# bank_34.net
KiCad netlist of a schematic drawn in Altium Designer
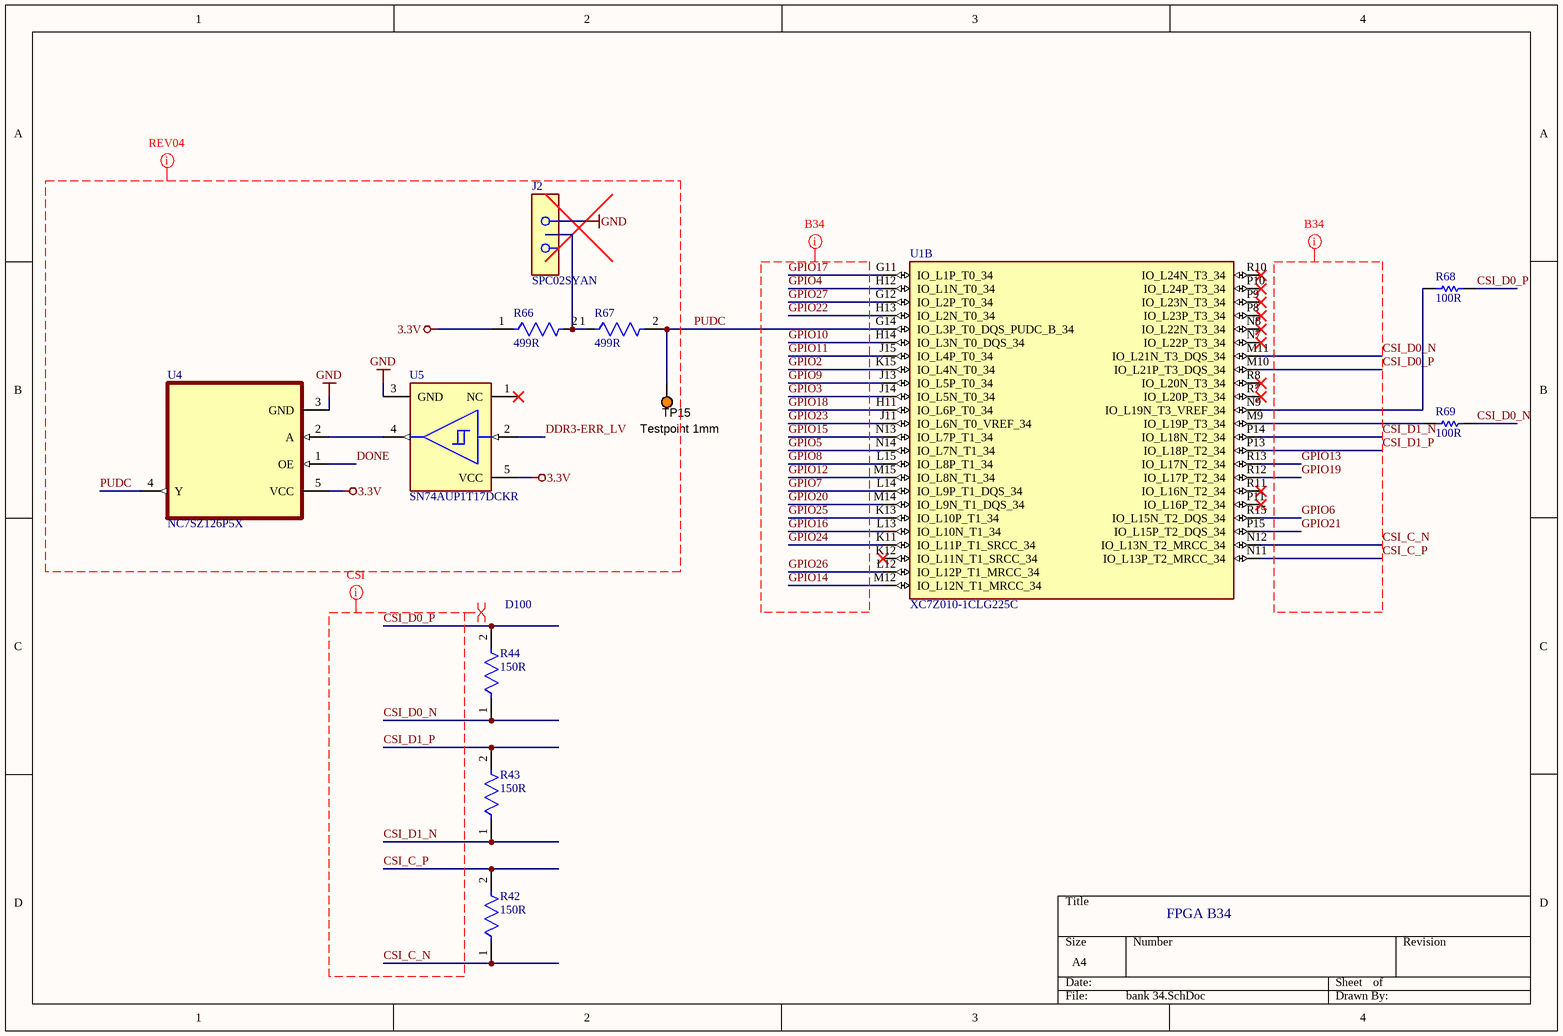
[diagram p0: bank 34.SchDoc]

(export (version "E")
  (design (tool "Eeschema 10.0.6"))
  (components
    (comp (ref "J2")
      (value "SPC02SYAN")
      (footprint "FP-SPC02SYAN-MFG")
      (description "CONN JUMPER SHORTING GOLD FLASH")
      (libsource (lib "Altium Content Vault") (part "728c6cbc3517dff9de184b23a534e16"))
    )
    (comp (ref "R42")
      (value "150R")
      (footprint "FP-RT0402-MFG")
      (description "RES SMD 150 OHM 0.1% 1/16W 0402")
      (fields
        (field (name "MANUFACTURER") "Yageo")
        (field (name "MANUFACTURER PART NUMBER") "RT0402BRD07150RL")
      )
      (libsource (lib "Altium Content Vault") (part "1029c3af85768c4190bb7ad29bc67b5"))
    )
    (comp (ref "R43")
      (value "150R")
      (footprint "FP-RT0402-MFG")
      (description "RES SMD 150 OHM 0.1% 1/16W 0402")
      (fields
        (field (name "MANUFACTURER") "Yageo")
        (field (name "MANUFACTURER PART NUMBER") "RT0402BRD07150RL")
      )
      (libsource (lib "Altium Content Vault") (part "1029c3af85768c4190bb7ad29bc67b5"))
    )
    (comp (ref "R44")
      (value "150R")
      (footprint "FP-RT0402-MFG")
      (description "RES SMD 150 OHM 0.1% 1/16W 0402")
      (fields
        (field (name "MANUFACTURER") "Yageo")
        (field (name "MANUFACTURER PART NUMBER") "RT0402BRD07150RL")
      )
      (libsource (lib "Altium Content Vault") (part "1029c3af85768c4190bb7ad29bc67b5"))
    )
    (comp (ref "R66")
      (value "499R")
      (footprint "FP-RQ731J-IPC_C")
      (description "RQ73 0603 499Ω  0.15W 10ppm/°C 0.1% 75V")
      (fields (field (name "MANUFACTURER") "TE") (field (name "TOLERANCE") "0.1%"))
      (libsource (lib "Altium Content Vault") (part "1029c3af85768c4190bb7ad29bc67b5"))
    )
    (comp (ref "R67")
      (value "499R")
      (footprint "FP-RQ731J-IPC_C")
      (description "RQ73 0603 499Ω  0.15W 10ppm/°C 0.1% 75V")
      (fields (field (name "MANUFACTURER") "TE") (field (name "TOLERANCE") "0.1%"))
      (libsource (lib "Altium Content Vault") (part "1029c3af85768c4190bb7ad29bc67b5"))
    )
    (comp (ref "R68")
      (value "100R")
      (footprint "RESC0603X28X15LL05T05")
      (fields (field (name "PART NUMBER") "CRCW0201100RJNED") (field (name "MANUFACTURER") "Vishay"))
      (libsource (lib "Altium Content Vault") (part "RES"))
    )
    (comp (ref "R69")
      (value "100R")
      (footprint "RESC0603X28X15LL05T05")
      (fields (field (name "PART NUMBER") "CRCW0201100RJNED") (field (name "MANUFACTURER") "Vishay"))
      (libsource (lib "Altium Content Vault") (part "RES"))
    )
    (comp (ref "TP15")
      (value "Testpoint 1mm")
      (footprint "KSTN-5003")
      (description "Test Point, Orange, 1-Pin THD, RoHS")
      (libsource (lib "Altium Content Vault") (part "TESTPOINT_ORANGE"))
    )
    (comp (ref "U1")
      (value "XC7Z010-1CLG225C")
      (footprint "BGA225C80P15X15_1300X1300X150")
      (fields (field (name "MF") "Xilinx Inc.") (field (name "DIGI-KEY_PART_NUMBER") "122-1855-ND"))
      (libsource (lib "XC7Z010-1CLG225C (2)") (part "XC7Z010-1CLG225C"))
    )
    (comp (ref "U4")
      (value "NC7SZ126P5X")
      (footprint "SOT65P210X110-5N")
      (description "Buffer, Non-Inverting 1 Element 1 Bit per Element 3-State Output SC-70-5")
      (fields (field (name "MF") "ON Semiconductor"))
      (libsource (lib "NC7SZ126P5X") (part "NC7SZ126P5X"))
    )
    (comp (ref "U5")
      (value "SN74AUP1T17DCKR")
      (footprint "FP-DCK0005A-IPC_B")
      (description "IC BUF NON-INVERT 3.6V SC70-5")
      (libsource (lib "Altium Content Vault") (part "13663c114c60c392ae5ab8dc83cb180"))
    )
  )
  (nets
    (net (code "1") (name "/CSI_C_N") (class "Default")
      (node (ref "R42") (pin "1") (pinfunction "1_1") (pintype "passive"))
      (node (ref "U1") (pin "N12") (pinfunction "IO_L13N_T2_MRCC_34_N12") (pintype "bidirectional"))
    )
    (net (code "2") (name "/CSI_C_P") (class "Default")
      (node (ref "R42") (pin "2") (pinfunction "2_2") (pintype "passive"))
      (node (ref "U1") (pin "N11") (pinfunction "IO_L13P_T2_MRCC_34_N11") (pintype "bidirectional"))
    )
    (net (code "3") (name "/CSI_D0_N") (class "Default")
      (node (ref "R44") (pin "1") (pinfunction "1_1") (pintype "passive"))
      (node (ref "R69") (pin "2") (pinfunction "2_2") (pintype "passive"))
      (node (ref "U1") (pin "M11") (pinfunction "IO_L21N_T3_DQS_34_M11") (pintype "bidirectional"))
    )
    (net (code "4") (name "/CSI_D0_P") (class "Default")
      (node (ref "R44") (pin "2") (pinfunction "2_2") (pintype "passive"))
      (node (ref "R68") (pin "2") (pinfunction "2_2") (pintype "passive"))
      (node (ref "U1") (pin "M10") (pinfunction "IO_L21P_T3_DQS_34_M10") (pintype "bidirectional"))
    )
    (net (code "5") (name "/CSI_D1_N") (class "Default")
      (node (ref "R43") (pin "1") (pinfunction "1_1") (pintype "passive"))
      (node (ref "U1") (pin "P14") (pinfunction "IO_L18N_T2_34_P14") (pintype "bidirectional"))
    )
    (net (code "6") (name "/CSI_D1_P") (class "Default")
      (node (ref "R43") (pin "2") (pinfunction "2_2") (pintype "passive"))
      (node (ref "U1") (pin "P13") (pinfunction "IO_L18P_T2_34_P13") (pintype "bidirectional"))
    )
    (net (code "7") (name "/DDR3-ERR_LV") (class "Default")
      (node (ref "U5") (pin "2") (pinfunction "A_2") (pintype "input"))
    )
    (net (code "8") (name "/DONE") (class "Default")
      (node (ref "U4") (pin "1") (pinfunction "OE_1") (pintype "input"))
    )
    (net (code "9") (name "/GPIO2") (class "Default")
      (node (ref "U1") (pin "K15") (pinfunction "IO_L4N_T0_34_K15") (pintype "bidirectional"))
    )
    (net (code "10") (name "/GPIO3") (class "Default")
      (node (ref "U1") (pin "J14") (pinfunction "IO_L5N_T0_34_J14") (pintype "bidirectional"))
    )
    (net (code "11") (name "/GPIO4") (class "Default")
      (node (ref "U1") (pin "H12") (pinfunction "IO_L1N_T0_34_H12") (pintype "bidirectional"))
    )
    (net (code "12") (name "/GPIO5") (class "Default")
      (node (ref "U1") (pin "N14") (pinfunction "IO_L7N_T1_34_N14") (pintype "bidirectional"))
    )
    (net (code "13") (name "/GPIO6") (class "Default")
      (node (ref "U1") (pin "R15") (pinfunction "IO_L15N_T2_DQS_34_R15") (pintype "bidirectional"))
    )
    (net (code "14") (name "/GPIO7") (class "Default")
      (node (ref "U1") (pin "L14") (pinfunction "IO_L9P_T1_DQS_34_L14") (pintype "bidirectional"))
    )
    (net (code "15") (name "/GPIO8") (class "Default")
      (node (ref "U1") (pin "L15") (pinfunction "IO_L8P_T1_34_L15") (pintype "bidirectional"))
    )
    (net (code "16") (name "/GPIO9") (class "Default")
      (node (ref "U1") (pin "J13") (pinfunction "IO_L5P_T0_34_J13") (pintype "bidirectional"))
    )
    (net (code "17") (name "/GPIO10") (class "Default")
      (node (ref "U1") (pin "H14") (pinfunction "IO_L3N_T0_DQS_34_H14") (pintype "bidirectional"))
    )
    (net (code "18") (name "/GPIO11") (class "Default")
      (node (ref "U1") (pin "J15") (pinfunction "IO_L4P_T0_34_J15") (pintype "bidirectional"))
    )
    (net (code "19") (name "/GPIO12") (class "Default")
      (node (ref "U1") (pin "M15") (pinfunction "IO_L8N_T1_34_M15") (pintype "bidirectional"))
    )
    (net (code "20") (name "/GPIO13") (class "Default")
      (node (ref "U1") (pin "R13") (pinfunction "IO_L17N_T2_34_R13") (pintype "bidirectional"))
    )
    (net (code "21") (name "/GPIO14") (class "Default")
      (node (ref "U1") (pin "M12") (pinfunction "IO_L12N_T1_MRCC_34_M12") (pintype "bidirectional"))
    )
    (net (code "22") (name "/GPIO15") (class "Default")
      (node (ref "U1") (pin "N13") (pinfunction "IO_L7P_T1_34_N13") (pintype "bidirectional"))
    )
    (net (code "23") (name "/GPIO16") (class "Default")
      (node (ref "U1") (pin "L13") (pinfunction "IO_L10N_T1_34_L13") (pintype "bidirectional"))
    )
    (net (code "24") (name "/GPIO17") (class "Default")
      (node (ref "U1") (pin "G11") (pinfunction "IO_L1P_T0_34_G11") (pintype "bidirectional"))
    )
    (net (code "25") (name "/GPIO18") (class "Default")
      (node (ref "U1") (pin "H11") (pinfunction "IO_L6P_T0_34_H11") (pintype "bidirectional"))
    )
    (net (code "26") (name "/GPIO19") (class "Default")
      (node (ref "U1") (pin "R12") (pinfunction "IO_L17P_T2_34_R12") (pintype "bidirectional"))
    )
    (net (code "27") (name "/GPIO20") (class "Default")
      (node (ref "U1") (pin "M14") (pinfunction "IO_L9N_T1_DQS_34_M14") (pintype "bidirectional"))
    )
    (net (code "28") (name "/GPIO21") (class "Default")
      (node (ref "U1") (pin "P15") (pinfunction "IO_L15P_T2_DQS_34_P15") (pintype "bidirectional"))
    )
    (net (code "29") (name "/GPIO22") (class "Default")
      (node (ref "U1") (pin "H13") (pinfunction "IO_L2N_T0_34_H13") (pintype "bidirectional"))
    )
    (net (code "30") (name "/GPIO23") (class "Default")
      (node (ref "U1") (pin "J11") (pinfunction "IO_L6N_T0_VREF_34_J11") (pintype "bidirectional"))
    )
    (net (code "31") (name "/GPIO24") (class "Default")
      (node (ref "U1") (pin "K11") (pinfunction "IO_L11P_T1_SRCC_34_K11") (pintype "bidirectional"))
    )
    (net (code "32") (name "/GPIO25") (class "Default")
      (node (ref "U1") (pin "K13") (pinfunction "IO_L10P_T1_34_K13") (pintype "bidirectional"))
    )
    (net (code "33") (name "/GPIO26") (class "Default")
      (node (ref "U1") (pin "L12") (pinfunction "IO_L12P_T1_MRCC_34_L12") (pintype "bidirectional"))
    )
    (net (code "34") (name "/GPIO27") (class "Default")
      (node (ref "U1") (pin "G12") (pinfunction "IO_L2P_T0_34_G12") (pintype "bidirectional"))
    )
    (net (code "35") (name "/PUDC") (class "Default")
      (node (ref "R67") (pin "2") (pinfunction "2_2") (pintype "passive"))
      (node (ref "TP15") (pin "1") (pinfunction "1_1") (pintype "passive"))
      (node (ref "U1") (pin "G14") (pinfunction "IO_L3P_T0_DQS_PUDC_B_34_G14") (pintype "bidirectional"))
      (node (ref "U4") (pin "4") (pinfunction "Y_4") (pintype "output"))
    )
    (net (code "36") (name "3.3V") (class "Default")
      (node (ref "R66") (pin "1") (pinfunction "1_1") (pintype "passive"))
      (node (ref "U4") (pin "5") (pinfunction "VCC_5") (pintype "power_in"))
      (node (ref "U5") (pin "5") (pinfunction "VCC_5") (pintype "power_in"))
    )
    (net (code "37") (name "GND") (class "Default")
      (node (ref "U4") (pin "3") (pinfunction "GND_3") (pintype "passive"))
      (node (ref "U5") (pin "3") (pinfunction "GND_3") (pintype "power_in"))
    )
    (net (code "38") (name "Net-(R66-Pad2)") (class "Default")
      (node (ref "R66") (pin "2") (pinfunction "2_2") (pintype "passive"))
      (node (ref "R67") (pin "1") (pinfunction "1_1") (pintype "passive"))
    )
    (net (code "39") (name "Net-(U1B-IO_L19N_T3_VREF_34)") (class "Default")
      (node (ref "R68") (pin "1") (pinfunction "1_1") (pintype "passive"))
      (node (ref "U1") (pin "N9") (pinfunction "IO_L19N_T3_VREF_34_N9") (pintype "bidirectional"))
    )
    (net (code "40") (name "Net-(U1B-IO_L19P_T3_34)") (class "Default")
      (node (ref "R69") (pin "1") (pinfunction "1_1") (pintype "passive"))
      (node (ref "U1") (pin "M9") (pinfunction "IO_L19P_T3_34_M9") (pintype "bidirectional"))
    )
    (net (code "41") (name "Net-(U4-A)") (class "Default")
      (node (ref "U4") (pin "2") (pinfunction "A_2") (pintype "input"))
      (node (ref "U5") (pin "4") (pinfunction "Y_4") (pintype "output"))
    )
    (net (code "42") (name "unconnected-(U1B-IO_L11N_T1_SRCC_34-PadK12)") (class "Default")
      (node (ref "U1") (pin "K12") (pinfunction "IO_L11N_T1_SRCC_34_K12") (pintype "bidirectional+no_connect"))
    )
    (net (code "43") (name "unconnected-(U1B-IO_L16N_T2_34-PadR11)") (class "Default")
      (node (ref "U1") (pin "R11") (pinfunction "IO_L16N_T2_34_R11") (pintype "bidirectional+no_connect"))
    )
    (net (code "44") (name "unconnected-(U1B-IO_L16P_T2_34-PadP11)") (class "Default")
      (node (ref "U1") (pin "P11") (pinfunction "IO_L16P_T2_34_P11") (pintype "bidirectional+no_connect"))
    )
    (net (code "45") (name "unconnected-(U1B-IO_L20N_T3_34-PadR8)") (class "Default")
      (node (ref "U1") (pin "R8") (pinfunction "IO_L20N_T3_34_R8") (pintype "bidirectional+no_connect"))
    )
    (net (code "46") (name "unconnected-(U1B-IO_L20P_T3_34-PadR7)") (class "Default")
      (node (ref "U1") (pin "R7") (pinfunction "IO_L20P_T3_34_R7") (pintype "bidirectional+no_connect"))
    )
    (net (code "47") (name "unconnected-(U1B-IO_L22N_T3_34-PadN8)") (class "Default")
      (node (ref "U1") (pin "N8") (pinfunction "IO_L22N_T3_34_N8") (pintype "bidirectional+no_connect"))
    )
    (net (code "48") (name "unconnected-(U1B-IO_L22P_T3_34-PadN7)") (class "Default")
      (node (ref "U1") (pin "N7") (pinfunction "IO_L22P_T3_34_N7") (pintype "bidirectional+no_connect"))
    )
    (net (code "49") (name "unconnected-(U1B-IO_L23N_T3_34-PadP9)") (class "Default")
      (node (ref "U1") (pin "P9") (pinfunction "IO_L23N_T3_34_P9") (pintype "bidirectional+no_connect"))
    )
    (net (code "50") (name "unconnected-(U1B-IO_L23P_T3_34-PadP8)") (class "Default")
      (node (ref "U1") (pin "P8") (pinfunction "IO_L23P_T3_34_P8") (pintype "bidirectional+no_connect"))
    )
    (net (code "51") (name "unconnected-(U1B-IO_L24N_T3_34-PadR10)") (class "Default")
      (node (ref "U1") (pin "R10") (pinfunction "IO_L24N_T3_34_R10") (pintype "bidirectional+no_connect"))
    )
    (net (code "52") (name "unconnected-(U1B-IO_L24P_T3_34-PadP10)") (class "Default")
      (node (ref "U1") (pin "P10") (pinfunction "IO_L24P_T3_34_P10") (pintype "bidirectional+no_connect"))
    )
    (net (code "53") (name "unconnected-(U5-NC-Pad1)") (class "Default")
      (node (ref "U5") (pin "1") (pinfunction "NC_1") (pintype "passive+no_connect"))
    )
  )
)
